# RoughGNSS.net
KiCad netlist of a schematic drawn in Altium Designer
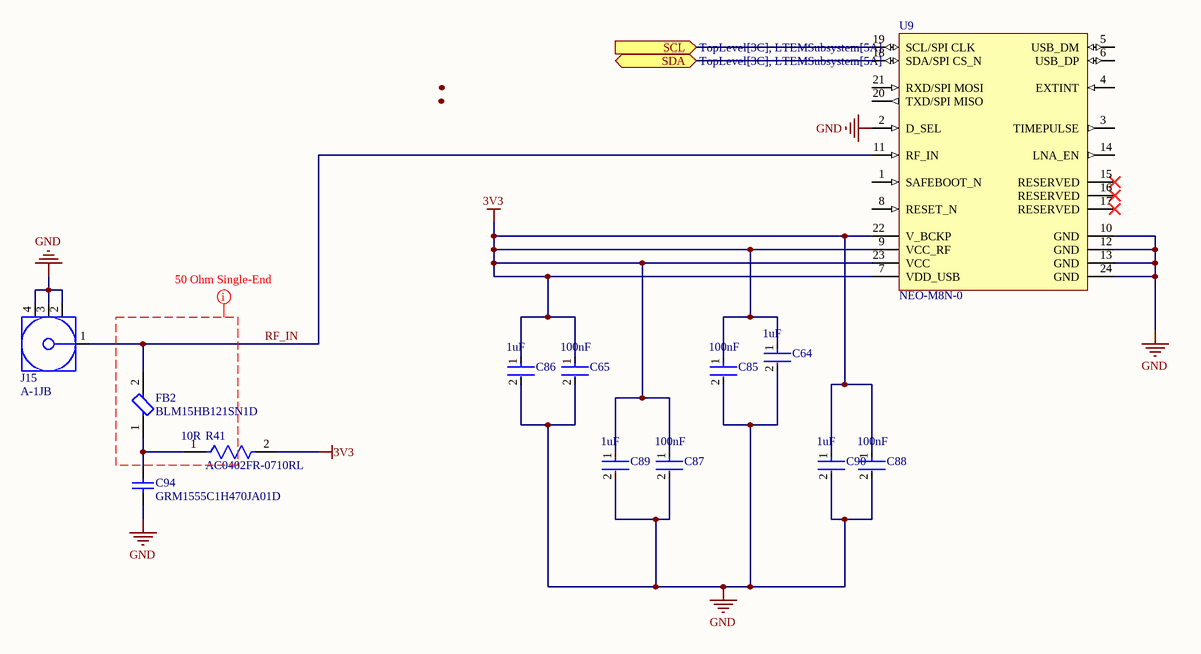
[diagram p0: RoughGNSS.SchDoc]

(export (version "E")
  (design (tool "Eeschema 10.0.6"))
  (components
    (comp (ref "C64")
      (value "CL05A105KP5NNNC")
      (footprint "FP-CL511-IPC_C")
      (description "Cap Ceramic 1uF 10V X5R ±10% SMD 0402 +85°C Paper T/R")
      (fields (field (name "CAPACITANCE") "1uF") (field (name "TOLERANCE") "10%"))
      (libsource (lib "Altium Content Vault") (part "b4654b650e69147ec39a6b967a45e02"))
    )
    (comp (ref "C65")
      (value "GRM155R71E104KE14J")
      (footprint "FP-GRM155-0_05-IPC_C")
      (description "Chip Multilayer Ceramic Capacitors for General Purpose, 0402, 0.10uF, X7R, 15%, 10%, 25V")
      (fields (field (name "CAPACITANCE") "100nF") (field (name "TOLERANCE") "10%"))
      (libsource (lib "Altium Content Vault") (part "02cd4be3c70576c341d710602a673aa"))
    )
    (comp (ref "C85")
      (value "GRM155R71E104KE14J")
      (footprint "FP-GRM155-0_05-IPC_C")
      (description "Chip Multilayer Ceramic Capacitors for General Purpose, 0402, 0.10uF, X7R, 15%, 10%, 25V")
      (fields (field (name "CAPACITANCE") "100nF") (field (name "TOLERANCE") "10%"))
      (libsource (lib "Altium Content Vault") (part "02cd4be3c70576c341d710602a673aa"))
    )
    (comp (ref "C86")
      (value "CL05A105KP5NNNC")
      (footprint "FP-CL511-IPC_C")
      (description "Cap Ceramic 1uF 10V X5R ±10% SMD 0402 +85°C Paper T/R")
      (fields (field (name "CAPACITANCE") "1uF") (field (name "TOLERANCE") "10%"))
      (libsource (lib "Altium Content Vault") (part "b4654b650e69147ec39a6b967a45e02"))
    )
    (comp (ref "C87")
      (value "GRM155R71E104KE14J")
      (footprint "FP-GRM155-0_05-IPC_C")
      (description "Chip Multilayer Ceramic Capacitors for General Purpose, 0402, 0.10uF, X7R, 15%, 10%, 25V")
      (fields (field (name "CAPACITANCE") "100nF") (field (name "TOLERANCE") "10%"))
      (libsource (lib "Altium Content Vault") (part "02cd4be3c70576c341d710602a673aa"))
    )
    (comp (ref "C88")
      (value "GRM155R71E104KE14J")
      (footprint "FP-GRM155-0_05-IPC_C")
      (description "Chip Multilayer Ceramic Capacitors for General Purpose, 0402, 0.10uF, X7R, 15%, 10%, 25V")
      (fields (field (name "CAPACITANCE") "100nF") (field (name "TOLERANCE") "10%"))
      (libsource (lib "Altium Content Vault") (part "02cd4be3c70576c341d710602a673aa"))
    )
    (comp (ref "C89")
      (value "CL05A105KP5NNNC")
      (footprint "FP-CL511-IPC_C")
      (description "Cap Ceramic 1uF 10V X5R ±10% SMD 0402 +85°C Paper T/R")
      (fields (field (name "CAPACITANCE") "1uF") (field (name "TOLERANCE") "10%"))
      (libsource (lib "Altium Content Vault") (part "b4654b650e69147ec39a6b967a45e02"))
    )
    (comp (ref "C90")
      (value "CL05A105KP5NNNC")
      (footprint "FP-CL511-IPC_C")
      (description "Cap Ceramic 1uF 10V X5R ±10% SMD 0402 +85°C Paper T/R")
      (fields (field (name "CAPACITANCE") "1uF") (field (name "TOLERANCE") "10%"))
      (libsource (lib "Altium Content Vault") (part "b4654b650e69147ec39a6b967a45e02"))
    )
    (comp (ref "C94")
      (value "GRM1555C1H470JA01D")
      (footprint "CAPC1005X55X25LL05T10")
      (fields (field (name "MANUFACTURER") "Murata"))
      (libsource (lib "Altium Content Vault") (part "CAP"))
    )
    (comp (ref "FB2")
      (value "BLM15HB121SN1D")
      (footprint "FP-BLM15-0_05-IPC_B")
      (description "Chip Ferrite Bead, 0402, 120Ω @ 100MHz, 0.7Ω, 25%, 300mA")
      (fields (field (name "TOLERANCE") "25%"))
      (libsource (lib "Altium Content Vault") (part "5f30dd21d616792df468990f7003faa"))
    )
    (comp (ref "J15")
      (value "A-1JB")
      (footprint "AMPH-A-1JB_V")
      (description "AMC PCB Jack, 0 to 60 GHz, 60 V, -40 to 90 degC, 4-Pin SMD, RoHS, Tape and Reel")
      (fields (field (name "TOLERANCE") "10%"))
      (libsource (lib "Altium Content Vault") (part "CN-S-3F-RF4"))
    )
    (comp (ref "R41")
      (value "AC0402FR-0710RL")
      (footprint "FP-AC0402-IPC_B")
      (description "RES 10Ω ±1% 0.063W 0402")
      (fields (field (name "TOLERANCE") "1%") (field (name "RESISTANCE") "10R"))
      (libsource (lib "Altium Content Vault") (part "1029c3af85768c4190bb7ad29bc67b5"))
    )
    (comp (ref "U9")
      (value "NEO-M8N-0")
      (footprint "UBX-NEO-M8-24_V")
      (description "U-Blox M8 Concurrent Gnss Module, 3.6 V, -40 to 85 degC, 24-Pin SMD, RoHS, Tape and Reel")
      (fields (field (name "MANUFACTURER") "U-Blox"))
      (libsource (lib "Altium Content Vault") (part "UBX-NEO-M8X-24"))
    )
  )
  (nets
    (net (code "1") (name "/RF_IN") (class "Default")
      (node (ref "FB2") (pin "2") (pinfunction "2_2") (pintype "passive"))
      (node (ref "J15") (pin "1") (pinfunction "1_1") (pintype "passive"))
      (node (ref "U9") (pin "11") (pinfunction "RF_IN_11") (pintype "input"))
    )
    (net (code "2") (name "/SCL") (class "Default")
      (node (ref "U9") (pin "19") (pinfunction "SCL/SPI_CLK_19") (pintype "bidirectional"))
    )
    (net (code "3") (name "/SDA") (class "Default")
      (node (ref "U9") (pin "18") (pinfunction "SDA/SPI_CS_N_18") (pintype "bidirectional"))
    )
    (net (code "4") (name "3V3") (class "Default")
      (node (ref "C64") (pin "1") (pinfunction "1_1") (pintype "passive"))
      (node (ref "C65") (pin "1") (pinfunction "1_1") (pintype "passive"))
      (node (ref "C85") (pin "1") (pinfunction "1_1") (pintype "passive"))
      (node (ref "C86") (pin "1") (pinfunction "1_1") (pintype "passive"))
      (node (ref "C87") (pin "1") (pinfunction "1_1") (pintype "passive"))
      (node (ref "C88") (pin "1") (pinfunction "1_1") (pintype "passive"))
      (node (ref "C89") (pin "1") (pinfunction "1_1") (pintype "passive"))
      (node (ref "C90") (pin "1") (pinfunction "1_1") (pintype "passive"))
      (node (ref "R41") (pin "2") (pinfunction "2_2") (pintype "passive"))
      (node (ref "U9") (pin "22") (pinfunction "V_BCKP_22") (pintype "power_in"))
      (node (ref "U9") (pin "23") (pinfunction "VCC_23") (pintype "power_in"))
      (node (ref "U9") (pin "7") (pinfunction "VDD_USB_7") (pintype "power_in"))
      (node (ref "U9") (pin "9") (pinfunction "VCC_RF_9") (pintype "power_in"))
    )
    (net (code "5") (name "GND") (class "Default")
      (node (ref "C64") (pin "2") (pinfunction "2_2") (pintype "passive"))
      (node (ref "C65") (pin "2") (pinfunction "2_2") (pintype "passive"))
      (node (ref "C85") (pin "2") (pinfunction "2_2") (pintype "passive"))
      (node (ref "C86") (pin "2") (pinfunction "2_2") (pintype "passive"))
      (node (ref "C87") (pin "2") (pinfunction "2_2") (pintype "passive"))
      (node (ref "C88") (pin "2") (pinfunction "2_2") (pintype "passive"))
      (node (ref "C89") (pin "2") (pinfunction "2_2") (pintype "passive"))
      (node (ref "C90") (pin "2") (pinfunction "2_2") (pintype "passive"))
      (node (ref "C94") (pin "1") (pinfunction "1_1") (pintype "passive"))
      (node (ref "J15") (pin "2") (pinfunction "2_2") (pintype "passive"))
      (node (ref "J15") (pin "3") (pinfunction "3_3") (pintype "passive"))
      (node (ref "J15") (pin "4") (pinfunction "4_4") (pintype "passive"))
      (node (ref "U9") (pin "10") (pinfunction "GND_10") (pintype "power_in"))
      (node (ref "U9") (pin "12") (pinfunction "GND_12") (pintype "power_in"))
      (node (ref "U9") (pin "13") (pinfunction "GND_13") (pintype "power_in"))
      (node (ref "U9") (pin "2") (pinfunction "D_SEL_2") (pintype "input"))
      (node (ref "U9") (pin "24") (pinfunction "GND_24") (pintype "power_in"))
    )
    (net (code "6") (name "Net-(C94-Pad2)") (class "Default")
      (node (ref "C94") (pin "2") (pinfunction "2_2") (pintype "passive"))
      (node (ref "FB2") (pin "1") (pinfunction "1_1") (pintype "passive"))
      (node (ref "R41") (pin "1") (pinfunction "1_1") (pintype "passive"))
    )
    (net (code "7") (name "unconnected-(U9-EXTINT-Pad4)") (class "Default")
      (node (ref "U9") (pin "4") (pinfunction "EXTINT_4") (pintype "input"))
    )
    (net (code "8") (name "unconnected-(U9-LNA_EN-Pad14)") (class "Default")
      (node (ref "U9") (pin "14") (pinfunction "LNA_EN_14") (pintype "output"))
    )
    (net (code "9") (name "unconnected-(U9-RESERVED-Pad15)") (class "Default")
      (node (ref "U9") (pin "15") (pinfunction "RESERVED_15") (pintype "passive+no_connect"))
    )
    (net (code "10") (name "unconnected-(U9-RESERVED-Pad16)") (class "Default")
      (node (ref "U9") (pin "16") (pinfunction "RESERVED_16") (pintype "passive+no_connect"))
    )
    (net (code "11") (name "unconnected-(U9-RESERVED-Pad17)") (class "Default")
      (node (ref "U9") (pin "17") (pinfunction "RESERVED_17") (pintype "passive+no_connect"))
    )
    (net (code "12") (name "unconnected-(U9-RESET_N-Pad8)") (class "Default")
      (node (ref "U9") (pin "8") (pinfunction "RESET_N_8") (pintype "input"))
    )
    (net (code "13") (name "unconnected-(U9-RXD{slash}SPI_MOSI-Pad21)") (class "Default")
      (node (ref "U9") (pin "21") (pinfunction "RXD/SPI_MOSI_21") (pintype "input"))
    )
    (net (code "14") (name "unconnected-(U9-SAFEBOOT_N-Pad1)") (class "Default")
      (node (ref "U9") (pin "1") (pinfunction "SAFEBOOT_N_1") (pintype "input"))
    )
    (net (code "15") (name "unconnected-(U9-TIMEPULSE-Pad3)") (class "Default")
      (node (ref "U9") (pin "3") (pinfunction "TIMEPULSE_3") (pintype "output"))
    )
    (net (code "16") (name "unconnected-(U9-TXD{slash}SPI_MISO-Pad20)") (class "Default")
      (node (ref "U9") (pin "20") (pinfunction "TXD/SPI_MISO_20") (pintype "output"))
    )
    (net (code "17") (name "unconnected-(U9-USB_DM-Pad5)") (class "Default")
      (node (ref "U9") (pin "5") (pinfunction "USB_DM_5") (pintype "bidirectional"))
    )
    (net (code "18") (name "unconnected-(U9-USB_DP-Pad6)") (class "Default")
      (node (ref "U9") (pin "6") (pinfunction "USB_DP_6") (pintype "bidirectional"))
    )
  )
)
